# B115B.net
KiCad netlist of a schematic drawn in EAGLE
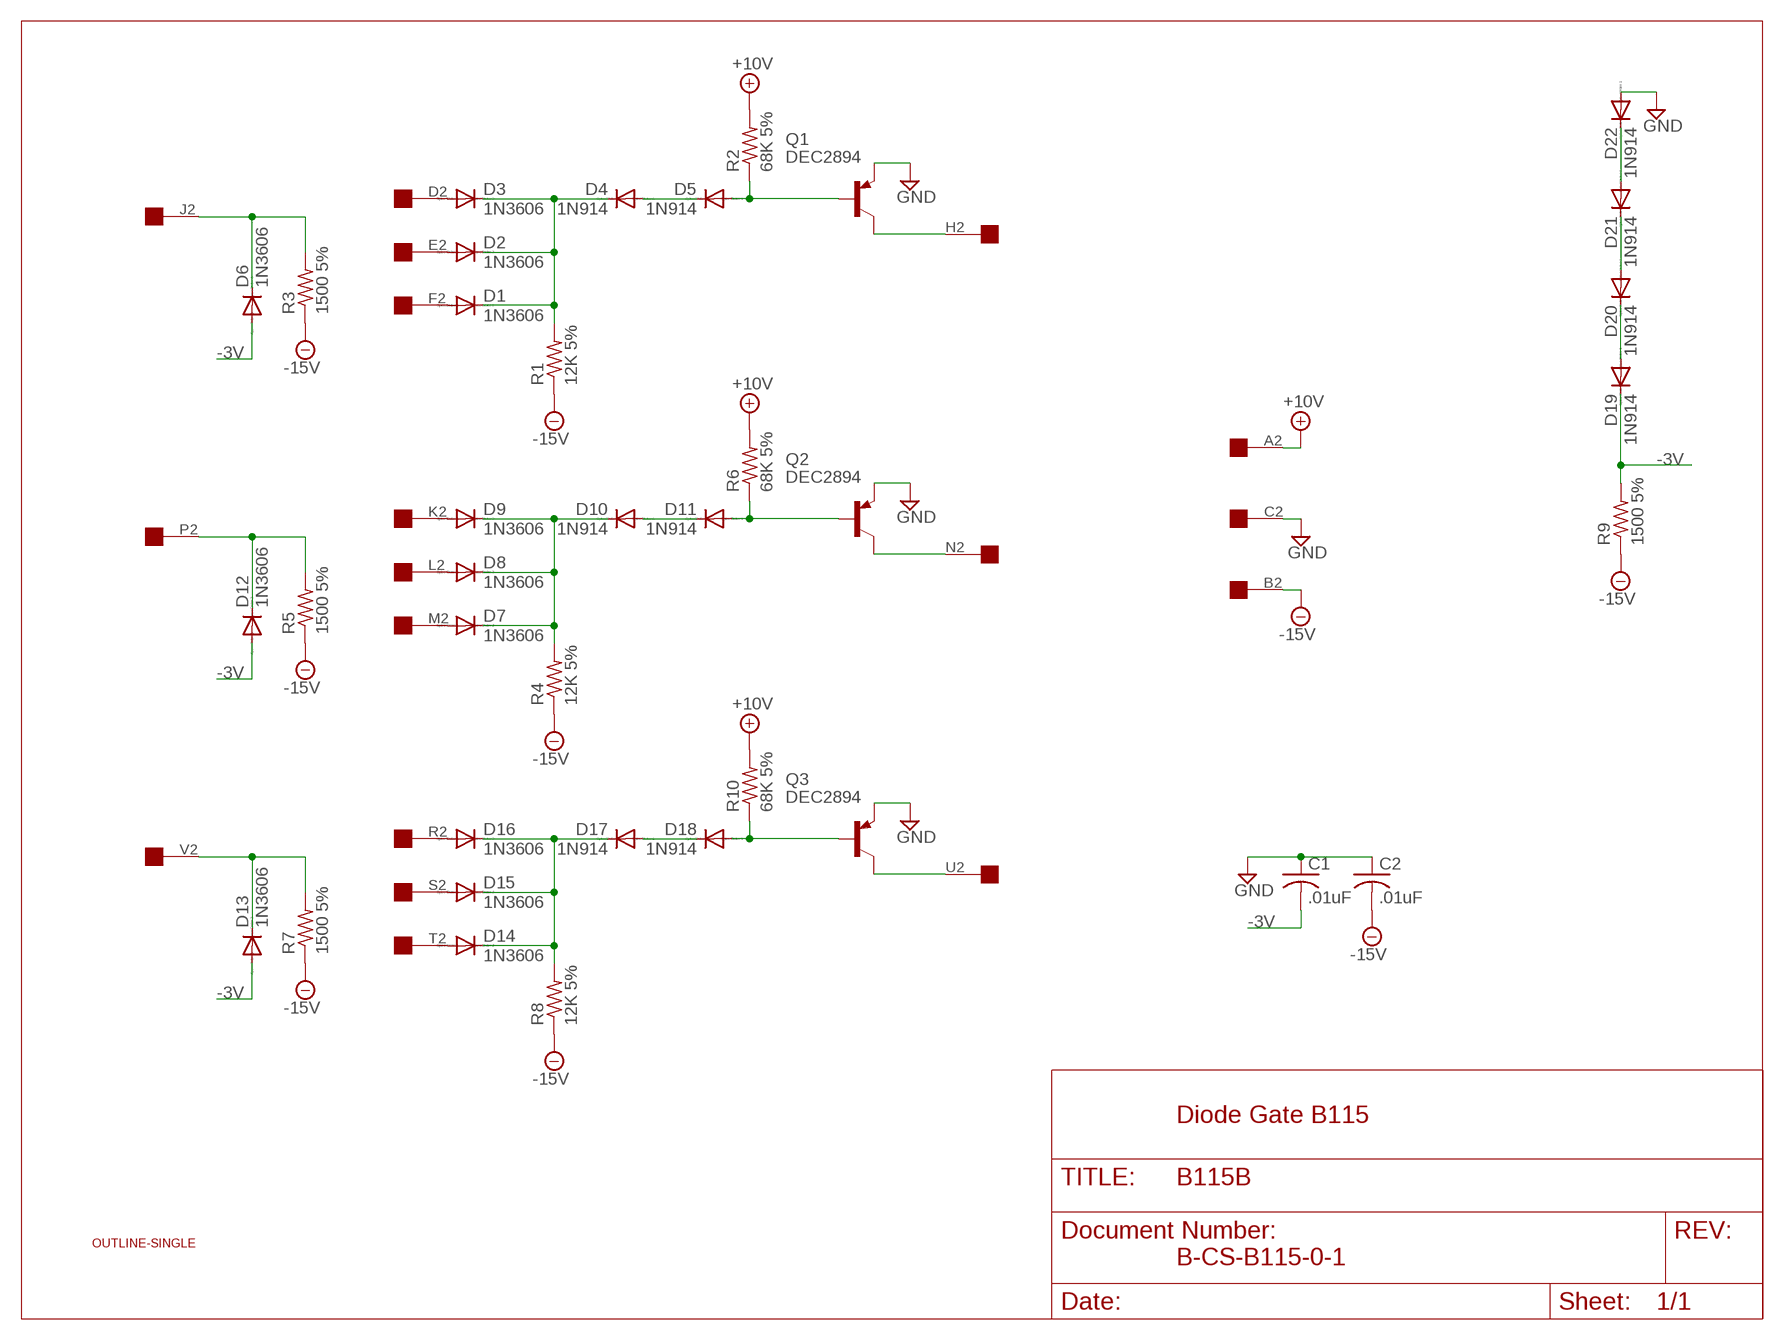
[diagram p0: schematic, sheet 1]

(export (version "E")
  (design (tool "Eeschema 10.0.6"))
  (components
    (comp (ref "C1")
      (value ".01uF")
      (footprint "eagle-import:C050-025X075")
      (libsource (lib "eagle-import") (part "C-US050-025X075"))
    )
    (comp (ref "C2")
      (value ".01uF")
      (footprint "eagle-import:C050-025X075")
      (libsource (lib "eagle-import") (part "C-US050-025X075"))
    )
    (comp (ref "D1")
      (value "1N3606")
      (footprint "eagle-import:DO35-10")
      (libsource (lib "eagle-import") (part "1N4148DO35-10"))
    )
    (comp (ref "D2")
      (value "1N3606")
      (footprint "eagle-import:DO35-10")
      (libsource (lib "eagle-import") (part "1N4148DO35-10"))
    )
    (comp (ref "D3")
      (value "1N3606")
      (footprint "eagle-import:DO35-10")
      (libsource (lib "eagle-import") (part "1N4148DO35-10"))
    )
    (comp (ref "D4")
      (value "1N914")
      (footprint "eagle-import:DO35-10")
      (libsource (lib "eagle-import") (part "1N4148DO35-10"))
    )
    (comp (ref "D5")
      (value "1N914")
      (footprint "eagle-import:DO35-10")
      (libsource (lib "eagle-import") (part "1N4148DO35-10"))
    )
    (comp (ref "D6")
      (value "1N3606")
      (footprint "eagle-import:DO35-10")
      (libsource (lib "eagle-import") (part "1N4148DO35-10"))
    )
    (comp (ref "D7")
      (value "1N3606")
      (footprint "eagle-import:DO35-10")
      (libsource (lib "eagle-import") (part "1N4148DO35-10"))
    )
    (comp (ref "D8")
      (value "1N3606")
      (footprint "eagle-import:DO35-10")
      (libsource (lib "eagle-import") (part "1N4148DO35-10"))
    )
    (comp (ref "D9")
      (value "1N3606")
      (footprint "eagle-import:DO35-10")
      (libsource (lib "eagle-import") (part "1N4148DO35-10"))
    )
    (comp (ref "D10")
      (value "1N914")
      (footprint "eagle-import:DO35-10")
      (libsource (lib "eagle-import") (part "1N4148DO35-10"))
    )
    (comp (ref "D11")
      (value "1N914")
      (footprint "eagle-import:DO35-10")
      (libsource (lib "eagle-import") (part "1N4148DO35-10"))
    )
    (comp (ref "D12")
      (value "1N3606")
      (footprint "eagle-import:DO35-10")
      (libsource (lib "eagle-import") (part "1N4148DO35-10"))
    )
    (comp (ref "D13")
      (value "1N3606")
      (footprint "eagle-import:DO35-10")
      (libsource (lib "eagle-import") (part "1N4148DO35-10"))
    )
    (comp (ref "D14")
      (value "1N3606")
      (footprint "eagle-import:DO35-10")
      (libsource (lib "eagle-import") (part "1N4148DO35-10"))
    )
    (comp (ref "D15")
      (value "1N3606")
      (footprint "eagle-import:DO35-10")
      (libsource (lib "eagle-import") (part "1N4148DO35-10"))
    )
    (comp (ref "D16")
      (value "1N3606")
      (footprint "eagle-import:DO35-10")
      (libsource (lib "eagle-import") (part "1N4148DO35-10"))
    )
    (comp (ref "D17")
      (value "1N914")
      (footprint "eagle-import:DO35-10")
      (libsource (lib "eagle-import") (part "1N4148DO35-10"))
    )
    (comp (ref "D18")
      (value "1N914")
      (footprint "eagle-import:DO35-10")
      (libsource (lib "eagle-import") (part "1N4148DO35-10"))
    )
    (comp (ref "D19")
      (value "1N914")
      (footprint "eagle-import:DO35-10")
      (libsource (lib "eagle-import") (part "1N4148DO35-10"))
    )
    (comp (ref "D20")
      (value "1N914")
      (footprint "eagle-import:DO35-10")
      (libsource (lib "eagle-import") (part "1N4148DO35-10"))
    )
    (comp (ref "D21")
      (value "1N914")
      (footprint "eagle-import:DO35-10")
      (libsource (lib "eagle-import") (part "1N4148DO35-10"))
    )
    (comp (ref "D22")
      (value "1N914")
      (footprint "eagle-import:DO35-10")
      (libsource (lib "eagle-import") (part "1N4148DO35-10"))
    )
    (comp (ref "Q1")
      (value "DEC2894")
      (footprint "eagle-import:TO39")
      (libsource (lib "eagle-import") (part "2N2904"))
    )
    (comp (ref "Q2")
      (value "DEC2894")
      (footprint "eagle-import:TO39")
      (libsource (lib "eagle-import") (part "2N2904"))
    )
    (comp (ref "Q3")
      (value "DEC2894")
      (footprint "eagle-import:TO39")
      (libsource (lib "eagle-import") (part "2N2904"))
    )
    (comp (ref "R1")
      (value "12K 5%")
      (footprint "eagle-import:0207_10")
      (libsource (lib "eagle-import") (part "R-US_0207/10"))
    )
    (comp (ref "R2")
      (value "68K 5%")
      (footprint "eagle-import:0207_10")
      (libsource (lib "eagle-import") (part "R-US_0207/10"))
    )
    (comp (ref "R3")
      (value "1500 5%")
      (footprint "eagle-import:0207_10")
      (libsource (lib "eagle-import") (part "R-US_0207/10"))
    )
    (comp (ref "R4")
      (value "12K 5%")
      (footprint "eagle-import:0207_10")
      (libsource (lib "eagle-import") (part "R-US_0207/10"))
    )
    (comp (ref "R5")
      (value "1500 5%")
      (footprint "eagle-import:0207_10")
      (libsource (lib "eagle-import") (part "R-US_0207/10"))
    )
    (comp (ref "R6")
      (value "68K 5%")
      (footprint "eagle-import:0207_10")
      (libsource (lib "eagle-import") (part "R-US_0207/10"))
    )
    (comp (ref "R7")
      (value "1500 5%")
      (footprint "eagle-import:0207_10")
      (libsource (lib "eagle-import") (part "R-US_0207/10"))
    )
    (comp (ref "R8")
      (value "12K 5%")
      (footprint "eagle-import:0207_10")
      (libsource (lib "eagle-import") (part "R-US_0207/10"))
    )
    (comp (ref "R9")
      (value "1500 5%")
      (footprint "eagle-import:0207_10")
      (libsource (lib "eagle-import") (part "R-US_0207/10"))
    )
    (comp (ref "R10")
      (value "68K 5%")
      (footprint "eagle-import:0207_10")
      (libsource (lib "eagle-import") (part "R-US_0207/10"))
    )
    (comp (ref "U$1")
      (value "OUTLINE-SINGLE")
      (footprint "eagle-import:SINGLE")
      (libsource (lib "eagle-import") (part "OUTLINE-SINGLE"))
    )
    (comp (ref "U$2")
      (value "EDGE-1")
      (footprint "eagle-import:EDGE-CON1")
      (libsource (lib "eagle-import") (part "EDGE-1"))
    )
  )
  (nets
    (net (code "1") (name "+10V") (class "Default")
      (node (ref "R10") (pin "2") (pinfunction "2_2") (pintype "passive"))
      (node (ref "R2") (pin "2") (pinfunction "2_2") (pintype "passive"))
      (node (ref "R6") (pin "2") (pinfunction "2_2") (pintype "passive"))
      (node (ref "U$2") (pin "A2") (pinfunction "1_A2") (pintype "bidirectional"))
    )
    (net (code "2") (name "-15V") (class "Default")
      (node (ref "C2") (pin "2") (pinfunction "2_2") (pintype "passive"))
      (node (ref "R1") (pin "1") (pinfunction "1_1") (pintype "passive"))
      (node (ref "R3") (pin "1") (pinfunction "1_1") (pintype "passive"))
      (node (ref "R4") (pin "1") (pinfunction "1_1") (pintype "passive"))
      (node (ref "R5") (pin "1") (pinfunction "1_1") (pintype "passive"))
      (node (ref "R7") (pin "1") (pinfunction "1_1") (pintype "passive"))
      (node (ref "R8") (pin "1") (pinfunction "1_1") (pintype "passive"))
      (node (ref "R9") (pin "1") (pinfunction "1_1") (pintype "passive"))
      (node (ref "U$2") (pin "B2") (pinfunction "1_B2") (pintype "bidirectional"))
    )
    (net (code "3") (name "/-3V") (class "Default")
      (node (ref "C1") (pin "2") (pinfunction "2_2") (pintype "passive"))
      (node (ref "D12") (pin "A") (pinfunction "A_A") (pintype "passive"))
      (node (ref "D13") (pin "A") (pinfunction "A_A") (pintype "passive"))
      (node (ref "D19") (pin "C") (pinfunction "C_C") (pintype "passive"))
      (node (ref "D6") (pin "A") (pinfunction "A_A") (pintype "passive"))
      (node (ref "R9") (pin "2") (pinfunction "2_2") (pintype "passive"))
    )
    (net (code "4") (name "GND") (class "Default")
      (node (ref "C1") (pin "1") (pinfunction "1_1") (pintype "passive"))
      (node (ref "C2") (pin "1") (pinfunction "1_1") (pintype "passive"))
      (node (ref "D22") (pin "A") (pinfunction "A_A") (pintype "passive"))
      (node (ref "Q1") (pin "1") (pinfunction "E_1") (pintype "passive"))
      (node (ref "Q2") (pin "1") (pinfunction "E_1") (pintype "passive"))
      (node (ref "Q3") (pin "1") (pinfunction "E_1") (pintype "passive"))
      (node (ref "U$2") (pin "C2") (pinfunction "1_C2") (pintype "bidirectional"))
    )
    (net (code "5") (name "Net-(D1-PadC)") (class "Default")
      (node (ref "D1") (pin "C") (pinfunction "C_C") (pintype "passive"))
      (node (ref "D2") (pin "C") (pinfunction "C_C") (pintype "passive"))
      (node (ref "D3") (pin "C") (pinfunction "C_C") (pintype "passive"))
      (node (ref "D4") (pin "C") (pinfunction "C_C") (pintype "passive"))
      (node (ref "R1") (pin "2") (pinfunction "2_2") (pintype "passive"))
    )
    (net (code "6") (name "Net-(D4-PadA)") (class "Default")
      (node (ref "D4") (pin "A") (pinfunction "A_A") (pintype "passive"))
      (node (ref "D5") (pin "C") (pinfunction "C_C") (pintype "passive"))
    )
    (net (code "7") (name "Net-(D10-PadA)") (class "Default")
      (node (ref "D10") (pin "A") (pinfunction "A_A") (pintype "passive"))
      (node (ref "D11") (pin "C") (pinfunction "C_C") (pintype "passive"))
    )
    (net (code "8") (name "Net-(D10-PadC)") (class "Default")
      (node (ref "D10") (pin "C") (pinfunction "C_C") (pintype "passive"))
      (node (ref "D7") (pin "C") (pinfunction "C_C") (pintype "passive"))
      (node (ref "D8") (pin "C") (pinfunction "C_C") (pintype "passive"))
      (node (ref "D9") (pin "C") (pinfunction "C_C") (pintype "passive"))
      (node (ref "R4") (pin "2") (pinfunction "2_2") (pintype "passive"))
    )
    (net (code "9") (name "Net-(D14-PadC)") (class "Default")
      (node (ref "D14") (pin "C") (pinfunction "C_C") (pintype "passive"))
      (node (ref "D15") (pin "C") (pinfunction "C_C") (pintype "passive"))
      (node (ref "D16") (pin "C") (pinfunction "C_C") (pintype "passive"))
      (node (ref "D17") (pin "C") (pinfunction "C_C") (pintype "passive"))
      (node (ref "R8") (pin "2") (pinfunction "2_2") (pintype "passive"))
    )
    (net (code "10") (name "Net-(D17-PadA)") (class "Default")
      (node (ref "D17") (pin "A") (pinfunction "A_A") (pintype "passive"))
      (node (ref "D18") (pin "C") (pinfunction "C_C") (pintype "passive"))
    )
    (net (code "11") (name "Net-(D19-PadA)") (class "Default")
      (node (ref "D19") (pin "A") (pinfunction "A_A") (pintype "passive"))
      (node (ref "D20") (pin "C") (pinfunction "C_C") (pintype "passive"))
    )
    (net (code "12") (name "Net-(D20-PadA)") (class "Default")
      (node (ref "D20") (pin "A") (pinfunction "A_A") (pintype "passive"))
      (node (ref "D21") (pin "C") (pinfunction "C_C") (pintype "passive"))
    )
    (net (code "13") (name "Net-(D21-PadA)") (class "Default")
      (node (ref "D21") (pin "A") (pinfunction "A_A") (pintype "passive"))
      (node (ref "D22") (pin "C") (pinfunction "C_C") (pintype "passive"))
    )
    (net (code "14") (name "Net-(Q1-B)") (class "Default")
      (node (ref "D5") (pin "A") (pinfunction "A_A") (pintype "passive"))
      (node (ref "Q1") (pin "2") (pinfunction "B_2") (pintype "passive"))
      (node (ref "R2") (pin "1") (pinfunction "1_1") (pintype "passive"))
    )
    (net (code "15") (name "Net-(Q1-C)") (class "Default")
      (node (ref "Q1") (pin "3") (pinfunction "C_3") (pintype "passive"))
      (node (ref "U$2") (pin "H2") (pinfunction "1_H2") (pintype "bidirectional"))
    )
    (net (code "16") (name "Net-(Q2-B)") (class "Default")
      (node (ref "D11") (pin "A") (pinfunction "A_A") (pintype "passive"))
      (node (ref "Q2") (pin "2") (pinfunction "B_2") (pintype "passive"))
      (node (ref "R6") (pin "1") (pinfunction "1_1") (pintype "passive"))
    )
    (net (code "17") (name "Net-(Q2-C)") (class "Default")
      (node (ref "Q2") (pin "3") (pinfunction "C_3") (pintype "passive"))
      (node (ref "U$2") (pin "N2") (pinfunction "1_N2") (pintype "bidirectional"))
    )
    (net (code "18") (name "Net-(Q3-B)") (class "Default")
      (node (ref "D18") (pin "A") (pinfunction "A_A") (pintype "passive"))
      (node (ref "Q3") (pin "2") (pinfunction "B_2") (pintype "passive"))
      (node (ref "R10") (pin "1") (pinfunction "1_1") (pintype "passive"))
    )
    (net (code "19") (name "Net-(Q3-C)") (class "Default")
      (node (ref "Q3") (pin "3") (pinfunction "C_3") (pintype "passive"))
      (node (ref "U$2") (pin "U2") (pinfunction "1_U2") (pintype "bidirectional"))
    )
    (net (code "20") (name "Net-(U$2D-1)") (class "Default")
      (node (ref "D3") (pin "A") (pinfunction "A_A") (pintype "passive"))
      (node (ref "U$2") (pin "D2") (pinfunction "1_D2") (pintype "bidirectional"))
    )
    (net (code "21") (name "Net-(U$2E-1)") (class "Default")
      (node (ref "D2") (pin "A") (pinfunction "A_A") (pintype "passive"))
      (node (ref "U$2") (pin "E2") (pinfunction "1_E2") (pintype "bidirectional"))
    )
    (net (code "22") (name "Net-(U$2F-1)") (class "Default")
      (node (ref "D1") (pin "A") (pinfunction "A_A") (pintype "passive"))
      (node (ref "U$2") (pin "F2") (pinfunction "1_F2") (pintype "bidirectional"))
    )
    (net (code "23") (name "Net-(U$2H-1)") (class "Default")
      (node (ref "D6") (pin "C") (pinfunction "C_C") (pintype "passive"))
      (node (ref "R3") (pin "2") (pinfunction "2_2") (pintype "passive"))
      (node (ref "U$2") (pin "J2") (pinfunction "1_J2") (pintype "bidirectional"))
    )
    (net (code "24") (name "Net-(U$2I-1)") (class "Default")
      (node (ref "D9") (pin "A") (pinfunction "A_A") (pintype "passive"))
      (node (ref "U$2") (pin "K2") (pinfunction "1_K2") (pintype "bidirectional"))
    )
    (net (code "25") (name "Net-(U$2J-1)") (class "Default")
      (node (ref "D8") (pin "A") (pinfunction "A_A") (pintype "passive"))
      (node (ref "U$2") (pin "L2") (pinfunction "1_L2") (pintype "bidirectional"))
    )
    (net (code "26") (name "Net-(U$2K-1)") (class "Default")
      (node (ref "D7") (pin "A") (pinfunction "A_A") (pintype "passive"))
      (node (ref "U$2") (pin "M2") (pinfunction "1_M2") (pintype "bidirectional"))
    )
    (net (code "27") (name "Net-(U$2M-1)") (class "Default")
      (node (ref "D12") (pin "C") (pinfunction "C_C") (pintype "passive"))
      (node (ref "R5") (pin "2") (pinfunction "2_2") (pintype "passive"))
      (node (ref "U$2") (pin "P2") (pinfunction "1_P2") (pintype "bidirectional"))
    )
    (net (code "28") (name "Net-(U$2N-1)") (class "Default")
      (node (ref "D16") (pin "A") (pinfunction "A_A") (pintype "passive"))
      (node (ref "U$2") (pin "R2") (pinfunction "1_R2") (pintype "bidirectional"))
    )
    (net (code "29") (name "Net-(U$2O-1)") (class "Default")
      (node (ref "D15") (pin "A") (pinfunction "A_A") (pintype "passive"))
      (node (ref "U$2") (pin "S2") (pinfunction "1_S2") (pintype "bidirectional"))
    )
    (net (code "30") (name "Net-(U$2P-1)") (class "Default")
      (node (ref "D14") (pin "A") (pinfunction "A_A") (pintype "passive"))
      (node (ref "U$2") (pin "T2") (pinfunction "1_T2") (pintype "bidirectional"))
    )
    (net (code "31") (name "Net-(U$2R-1)") (class "Default")
      (node (ref "D13") (pin "C") (pinfunction "C_C") (pintype "passive"))
      (node (ref "R7") (pin "2") (pinfunction "2_2") (pintype "passive"))
      (node (ref "U$2") (pin "V2") (pinfunction "1_V2") (pintype "bidirectional"))
    )
  )
)
